# N40P107_Breakout.net
KiCad netlist of a schematic drawn in EAGLE
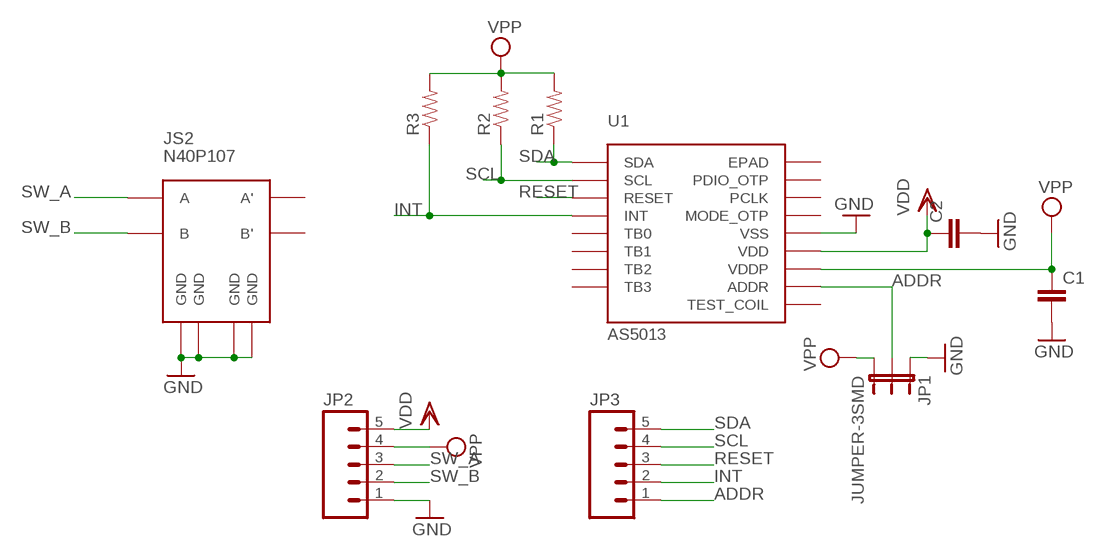
[diagram p0: schematic, sheet 1]

(export (version "E")
  (design (tool "Eeschema 10.0.6"))
  (components
    (comp (ref "C1")
      (value "CAP0603-CAP")
      (footprint "eagle-import:0603-CAP")
      (libsource (lib "eagle-import") (part "CAP0603-CAP"))
    )
    (comp (ref "C2")
      (value "CAP0603-CAP")
      (footprint "eagle-import:0603-CAP")
      (libsource (lib "eagle-import") (part "CAP0603-CAP"))
    )
    (comp (ref "JP1")
      (value "JUMPER-3SMD")
      (footprint "eagle-import:SJ_3")
      (libsource (lib "eagle-import") (part "JUMPER-3SMD"))
    )
    (comp (ref "JP2")
      (value "M05PTH")
      (footprint "eagle-import:1X05")
      (libsource (lib "eagle-import") (part "M05PTH"))
    )
    (comp (ref "JP3")
      (value "M05PTH")
      (footprint "eagle-import:1X05")
      (libsource (lib "eagle-import") (part "M05PTH"))
    )
    (comp (ref "JS2")
      (value "N40P107")
      (footprint "eagle-import:N40P107")
      (libsource (lib "eagle-import") (part "N40P107"))
    )
    (comp (ref "R1")
      (value "RESISTOR0402-RES")
      (footprint "eagle-import:0402-RES")
      (libsource (lib "eagle-import") (part "RESISTOR0402-RES"))
    )
    (comp (ref "R2")
      (value "RESISTOR0402-RES")
      (footprint "eagle-import:0402-RES")
      (libsource (lib "eagle-import") (part "RESISTOR0402-RES"))
    )
    (comp (ref "R3")
      (value "RESISTOR0402-RES")
      (footprint "eagle-import:0402-RES")
      (libsource (lib "eagle-import") (part "RESISTOR0402-RES"))
    )
    (comp (ref "U1")
      (value "AS5013")
      (footprint "eagle-import:AS5013")
      (libsource (lib "eagle-import") (part "AS5013"))
    )
  )
  (nets
    (net (code "1") (name "/ADDR") (class "Default")
      (node (ref "JP1") (pin "2") (pinfunction "2_2") (pintype "passive"))
      (node (ref "JP3") (pin "1") (pinfunction "1_1") (pintype "passive"))
      (node (ref "U1") (pin "10") (pinfunction "ADDR_10") (pintype "bidirectional"))
    )
    (net (code "2") (name "/INT") (class "Default")
      (node (ref "JP3") (pin "2") (pinfunction "2_2") (pintype "passive"))
      (node (ref "R3") (pin "1") (pinfunction "1_1") (pintype "passive"))
      (node (ref "U1") (pin "4") (pinfunction "INT_4") (pintype "bidirectional"))
    )
    (net (code "3") (name "/RESET") (class "Default")
      (node (ref "JP3") (pin "3") (pinfunction "3_3") (pintype "passive"))
      (node (ref "U1") (pin "3") (pinfunction "RESET_3") (pintype "bidirectional"))
    )
    (net (code "4") (name "/SCL") (class "Default")
      (node (ref "JP3") (pin "4") (pinfunction "4_4") (pintype "passive"))
      (node (ref "R2") (pin "1") (pinfunction "1_1") (pintype "passive"))
      (node (ref "U1") (pin "2") (pinfunction "SCL_2") (pintype "bidirectional"))
    )
    (net (code "5") (name "/SDA") (class "Default")
      (node (ref "JP3") (pin "5") (pinfunction "5_5") (pintype "passive"))
      (node (ref "R1") (pin "1") (pinfunction "1_1") (pintype "passive"))
      (node (ref "U1") (pin "1") (pinfunction "SDA_1") (pintype "bidirectional"))
    )
    (net (code "6") (name "/SW_A") (class "Default")
      (node (ref "JP2") (pin "3") (pinfunction "3_3") (pintype "passive"))
      (node (ref "JS2") (pin "2") (pinfunction "A_2") (pintype "bidirectional"))
    )
    (net (code "7") (name "/SW_B") (class "Default")
      (node (ref "JP2") (pin "2") (pinfunction "2_2") (pintype "passive"))
      (node (ref "JS2") (pin "3") (pinfunction "B_3") (pintype "bidirectional"))
    )
    (net (code "8") (name "GND") (class "Default")
      (node (ref "C1") (pin "2") (pinfunction "2_2") (pintype "passive"))
      (node (ref "C2") (pin "2") (pinfunction "2_2") (pintype "passive"))
      (node (ref "JP1") (pin "1") (pinfunction "1_1") (pintype "passive"))
      (node (ref "JP2") (pin "1") (pinfunction "1_1") (pintype "passive"))
      (node (ref "JS2") (pin "1") (pinfunction "GND_1") (pintype "bidirectional"))
      (node (ref "JS2") (pin "4") (pinfunction "GND_4") (pintype "bidirectional"))
      (node (ref "JS2") (pin "5") (pinfunction "GND_5") (pintype "bidirectional"))
      (node (ref "JS2") (pin "8") (pinfunction "GND_8") (pintype "bidirectional"))
      (node (ref "U1") (pin "13") (pinfunction "VSS_13") (pintype "bidirectional"))
    )
    (net (code "9") (name "VDD") (class "Default")
      (node (ref "C2") (pin "1") (pinfunction "1_1") (pintype "passive"))
      (node (ref "JP2") (pin "5") (pinfunction "5_5") (pintype "passive"))
      (node (ref "U1") (pin "12") (pinfunction "VDD_12") (pintype "bidirectional"))
    )
    (net (code "10") (name "VPP") (class "Default")
      (node (ref "C1") (pin "1") (pinfunction "1_1") (pintype "passive"))
      (node (ref "JP1") (pin "3") (pinfunction "3_3") (pintype "passive"))
      (node (ref "JP2") (pin "4") (pinfunction "4_4") (pintype "passive"))
      (node (ref "R1") (pin "2") (pinfunction "2_2") (pintype "passive"))
      (node (ref "R2") (pin "2") (pinfunction "2_2") (pintype "passive"))
      (node (ref "R3") (pin "2") (pinfunction "2_2") (pintype "passive"))
      (node (ref "U1") (pin "11") (pinfunction "VDDP_11") (pintype "bidirectional"))
    )
    (net (code "11") (name "unconnected-(JS2-A'-Pad7)") (class "Default")
      (node (ref "JS2") (pin "7") (pinfunction "A'_7") (pintype "bidirectional"))
    )
    (net (code "12") (name "unconnected-(JS2-B'-Pad6)") (class "Default")
      (node (ref "JS2") (pin "6") (pinfunction "B'_6") (pintype "bidirectional"))
    )
    (net (code "13") (name "unconnected-(U1-EPAD-Pad17)") (class "Default")
      (node (ref "U1") (pin "17") (pinfunction "EPAD_17") (pintype "bidirectional"))
    )
    (net (code "14") (name "unconnected-(U1-MODE_OTP-Pad14)") (class "Default")
      (node (ref "U1") (pin "14") (pinfunction "MODE_OTP_14") (pintype "bidirectional"))
    )
    (net (code "15") (name "unconnected-(U1-PCLK-Pad15)") (class "Default")
      (node (ref "U1") (pin "15") (pinfunction "PCLK_15") (pintype "bidirectional"))
    )
    (net (code "16") (name "unconnected-(U1-PDIO_OTP-Pad16)") (class "Default")
      (node (ref "U1") (pin "16") (pinfunction "PDIO_OTP_16") (pintype "bidirectional"))
    )
    (net (code "17") (name "unconnected-(U1-TB0-Pad5)") (class "Default")
      (node (ref "U1") (pin "5") (pinfunction "TB0_5") (pintype "bidirectional"))
    )
    (net (code "18") (name "unconnected-(U1-TB1-Pad6)") (class "Default")
      (node (ref "U1") (pin "6") (pinfunction "TB1_6") (pintype "bidirectional"))
    )
    (net (code "19") (name "unconnected-(U1-TB2-Pad7)") (class "Default")
      (node (ref "U1") (pin "7") (pinfunction "TB2_7") (pintype "bidirectional"))
    )
    (net (code "20") (name "unconnected-(U1-TB3-Pad8)") (class "Default")
      (node (ref "U1") (pin "8") (pinfunction "TB3_8") (pintype "bidirectional"))
    )
    (net (code "21") (name "unconnected-(U1-TEST_COIL-Pad9)") (class "Default")
      (node (ref "U1") (pin "9") (pinfunction "TEST_COIL_9") (pintype "bidirectional"))
    )
  )
)
